# PHY_SFC.net
KiCad netlist of a schematic drawn in Altium Designer
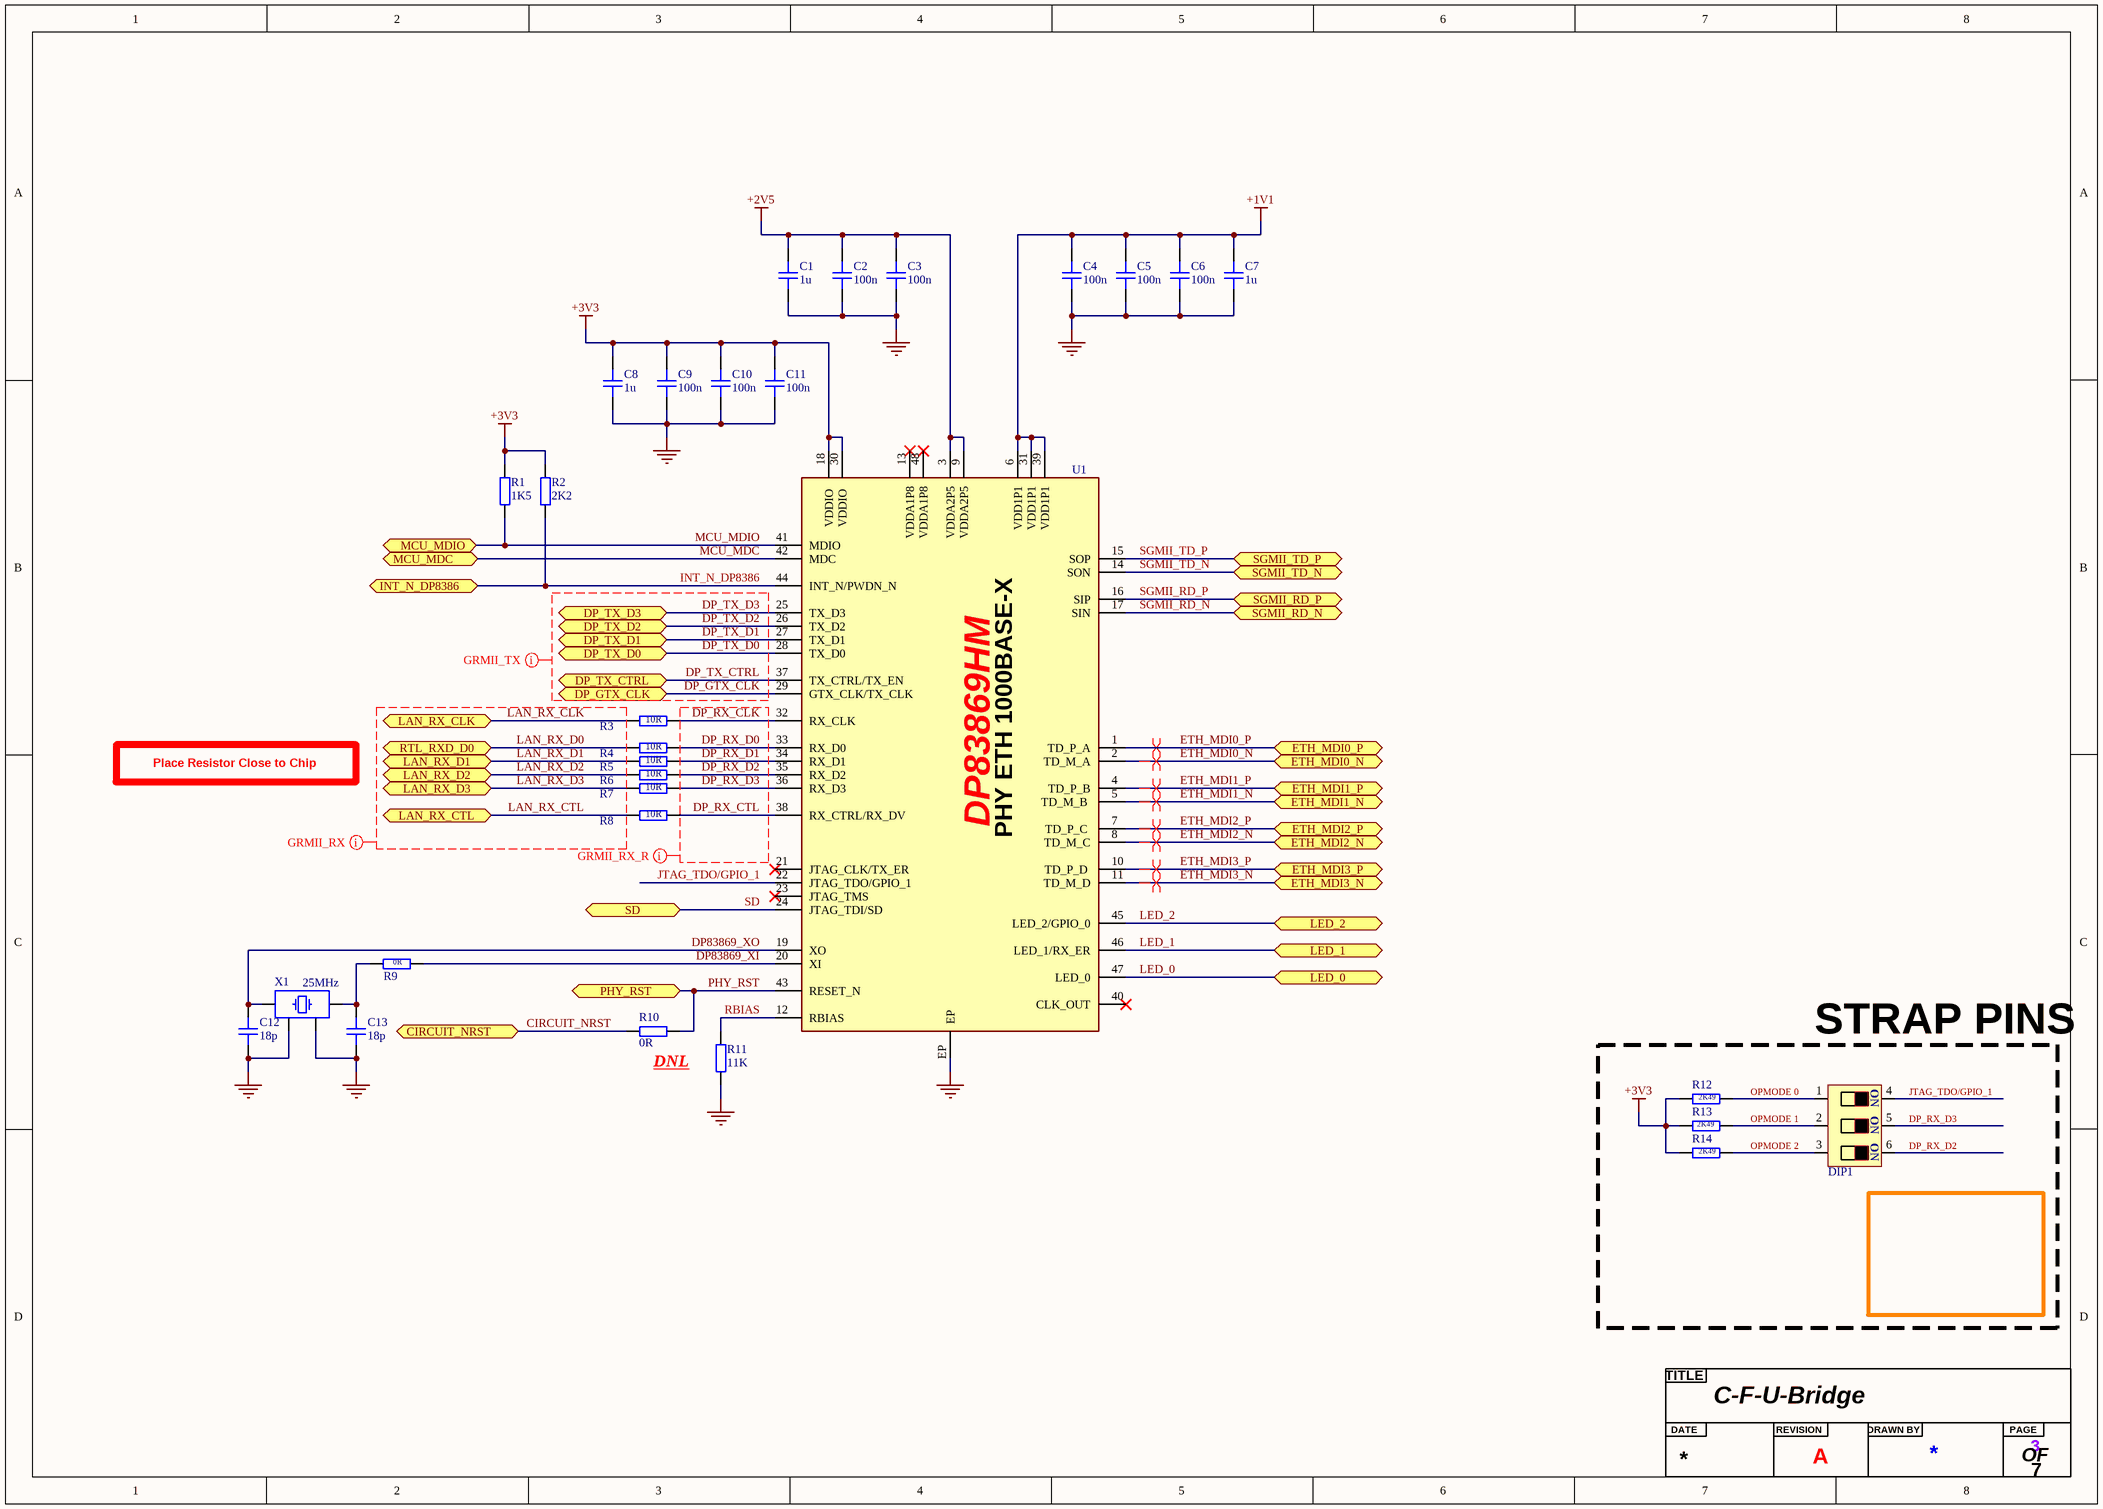
[diagram p0: PHY SFC.SchDoc]

(export (version "E")
  (design (tool "Eeschema 10.0.6"))
  (components
    (comp (ref "C1")
      (value "1u")
      (footprint "CAP_0603")
      (description "[C15849]")
      (libsource (lib "Schematic-Lib-PhilsLab") (part "CAP_0603"))
    )
    (comp (ref "C2")
      (value "100n")
      (footprint "CAP_0603")
      (description "[C14663]")
      (libsource (lib "Schematic-Lib-PhilsLab") (part "CAP_0603"))
    )
    (comp (ref "C3")
      (value "100n")
      (footprint "CAP_0603")
      (description "[C14663]")
      (libsource (lib "Schematic-Lib-PhilsLab") (part "CAP_0603"))
    )
    (comp (ref "C4")
      (value "100n")
      (footprint "CAP_0603")
      (description "[C14663]")
      (libsource (lib "Schematic-Lib-PhilsLab") (part "CAP_0603"))
    )
    (comp (ref "C5")
      (value "100n")
      (footprint "CAP_0603")
      (description "[C14663]")
      (libsource (lib "Schematic-Lib-PhilsLab") (part "CAP_0603"))
    )
    (comp (ref "C6")
      (value "100n")
      (footprint "CAP_0603")
      (description "[C14663]")
      (libsource (lib "Schematic-Lib-PhilsLab") (part "CAP_0603"))
    )
    (comp (ref "C7")
      (value "1u")
      (footprint "CAP_0603")
      (description "[C15849]")
      (libsource (lib "Schematic-Lib-PhilsLab") (part "CAP_0603"))
    )
    (comp (ref "C8")
      (value "1u")
      (footprint "CAP_0603")
      (description "[C15849]")
      (libsource (lib "Schematic-Lib-PhilsLab") (part "CAP_0603"))
    )
    (comp (ref "C9")
      (value "100n")
      (footprint "CAP_0603")
      (description "[C14663]")
      (libsource (lib "Schematic-Lib-PhilsLab") (part "CAP_0603"))
    )
    (comp (ref "C10")
      (value "100n")
      (footprint "CAP_0603")
      (description "[C14663]")
      (libsource (lib "Schematic-Lib-PhilsLab") (part "CAP_0603"))
    )
    (comp (ref "C11")
      (value "100n")
      (footprint "CAP_0603")
      (description "[C14663]")
      (libsource (lib "Schematic-Lib-PhilsLab") (part "CAP_0603"))
    )
    (comp (ref "C12")
      (value "18p")
      (footprint "CAP_0402")
      (description "Capacitor SMD 0402 [C1549]")
      (libsource (lib "Schematic-Lib-PhilsLab") (part "CAP_0402"))
    )
    (comp (ref "C13")
      (value "18p")
      (footprint "CAP_0402")
      (description "Capacitor SMD 0402 [C1549]")
      (libsource (lib "Schematic-Lib-PhilsLab") (part "CAP_0402"))
    )
    (comp (ref "DIP1")
      (value "3 POS DIP SWITCH")
      (footprint "DSWB03LHGET")
      (description "[C99420]")
      (libsource (lib "My_Library") (part "DSWB03LHGET"))
    )
    (comp (ref "R1")
      (value "1K5")
      (footprint "RES_0603")
      (description "[C22843]")
      (libsource (lib "Schematic-Lib-PhilsLab") (part "RES_0603"))
    )
    (comp (ref "R2")
      (value "2K2")
      (footprint "RES_0603")
      (description "[C4190]")
      (libsource (lib "Schematic-Lib-PhilsLab") (part "RES_0603"))
    )
    (comp (ref "R3")
      (value "10R")
      (footprint "RES_0402")
      (description "[C25077]")
      (libsource (lib "Schematic-Lib-PhilsLab") (part "RES_0402"))
    )
    (comp (ref "R4")
      (value "10R")
      (footprint "RES_0402")
      (description "[C25077]")
      (libsource (lib "Schematic-Lib-PhilsLab") (part "RES_0402"))
    )
    (comp (ref "R5")
      (value "10R")
      (footprint "RES_0402")
      (description "[C25077]")
      (libsource (lib "Schematic-Lib-PhilsLab") (part "RES_0402"))
    )
    (comp (ref "R6")
      (value "10R")
      (footprint "RES_0402")
      (description "[C25077]")
      (libsource (lib "Schematic-Lib-PhilsLab") (part "RES_0402"))
    )
    (comp (ref "R7")
      (value "10R")
      (footprint "RES_0402")
      (description "[C25077]")
      (libsource (lib "Schematic-Lib-PhilsLab") (part "RES_0402"))
    )
    (comp (ref "R8")
      (value "10R")
      (footprint "RES_0402")
      (description "[C25077]")
      (libsource (lib "Schematic-Lib-PhilsLab") (part "RES_0402"))
    )
    (comp (ref "R9")
      (value "0R")
      (footprint "RES_0402")
      (description "Resistor SMD 0402 [C17168]")
      (libsource (lib "Schematic-Lib-PhilsLab") (part "RES_0402"))
    )
    (comp (ref "R10")
      (value "0R")
      (footprint "RES_0603")
      (libsource (lib "Schematic-Lib-PhilsLab") (part "RES_0603"))
    )
    (comp (ref "R11")
      (value "11K")
      (footprint "RES_0603")
      (description "[C25950]")
      (libsource (lib "Schematic-Lib-PhilsLab") (part "RES_0603"))
    )
    (comp (ref "R12")
      (value "2K49")
      (footprint "RES_0603")
      (description "[C22908]")
      (libsource (lib "Schematic-Lib-PhilsLab") (part "RES_0603"))
    )
    (comp (ref "R13")
      (value "2K49")
      (footprint "RES_0603")
      (description "[C22908]")
      (libsource (lib "Schematic-Lib-PhilsLab") (part "RES_0603"))
    )
    (comp (ref "R14")
      (value "2K49")
      (footprint "RES_0603")
      (description "[C22908]")
      (libsource (lib "Schematic-Lib-PhilsLab") (part "RES_0603"))
    )
    (comp (ref "U1")
      (value "PHY ETH 1000BASE-X/1000BASE-T")
      (footprint "DP83869HMRGZT")
      (description "[C2671580]")
      (libsource (lib "My_Library") (part "DP83869HMRGZT"))
    )
    (comp (ref "X1")
      (value "25MHz")
      (footprint "XTAL_3225")
      (description "Crystal SMD 24MHz 10PPM 7pF 3225 [C9006]")
      (fields
        (field (name "MANUFACTURER") "Epson")
        (field (name "MANUFACTURER PART NUMBER") "TSX-3225 24.0000MF15X-AC")
      )
      (libsource (lib "Schematic-Lib-PhilsLab") (part "TSX-3225_24.0000MF15X-AC"))
    )
  )
  (nets
    (net (code "1") (name "+1V1") (class "Default")
      (node (ref "C4") (pin "2") (pinfunction "2_2") (pintype "passive"))
      (node (ref "C5") (pin "2") (pinfunction "2_2") (pintype "passive"))
      (node (ref "C6") (pin "2") (pinfunction "2_2") (pintype "passive"))
      (node (ref "C7") (pin "2") (pinfunction "2_2") (pintype "passive"))
      (node (ref "U1") (pin "31") (pinfunction "VDD1P1_31") (pintype "passive"))
      (node (ref "U1") (pin "39") (pinfunction "VDD1P1_39") (pintype "passive"))
      (node (ref "U1") (pin "6") (pinfunction "VDD1P1_6") (pintype "passive"))
    )
    (net (code "2") (name "+2V5") (class "Default")
      (node (ref "C1") (pin "2") (pinfunction "2_2") (pintype "passive"))
      (node (ref "C2") (pin "2") (pinfunction "2_2") (pintype "passive"))
      (node (ref "C3") (pin "2") (pinfunction "2_2") (pintype "passive"))
      (node (ref "U1") (pin "3") (pinfunction "VDDA2P5_3") (pintype "passive"))
      (node (ref "U1") (pin "9") (pinfunction "VDDA2P5_9") (pintype "passive"))
    )
    (net (code "3") (name "+3V3") (class "Default")
      (node (ref "C10") (pin "2") (pinfunction "2_2") (pintype "passive"))
      (node (ref "C11") (pin "2") (pinfunction "2_2") (pintype "passive"))
      (node (ref "C8") (pin "2") (pinfunction "2_2") (pintype "passive"))
      (node (ref "C9") (pin "2") (pinfunction "2_2") (pintype "passive"))
      (node (ref "R1") (pin "2") (pinfunction "2_2") (pintype "passive"))
      (node (ref "R12") (pin "2") (pinfunction "2_2") (pintype "passive"))
      (node (ref "R13") (pin "2") (pinfunction "2_2") (pintype "passive"))
      (node (ref "R14") (pin "2") (pinfunction "2_2") (pintype "passive"))
      (node (ref "R2") (pin "2") (pinfunction "2_2") (pintype "passive"))
      (node (ref "U1") (pin "18") (pinfunction "VDDIO_18") (pintype "passive"))
      (node (ref "U1") (pin "30") (pinfunction "VDDIO_30") (pintype "passive"))
    )
    (net (code "4") (name "/CIRCUIT_NRST") (class "Default")
      (node (ref "R10") (pin "1") (pinfunction "1_1") (pintype "passive"))
    )
    (net (code "5") (name "/DP83869_XI") (class "Default")
      (node (ref "R9") (pin "2") (pinfunction "2_2") (pintype "passive"))
      (node (ref "U1") (pin "20") (pinfunction "XI_20") (pintype "passive"))
    )
    (net (code "6") (name "/DP83869_XO") (class "Default")
      (node (ref "C12") (pin "2") (pinfunction "2_2") (pintype "passive"))
      (node (ref "U1") (pin "19") (pinfunction "XO_19") (pintype "passive"))
      (node (ref "X1") (pin "3") (pinfunction "3_3") (pintype "passive"))
    )
    (net (code "7") (name "/DP_GTX_CLK") (class "Default")
      (node (ref "U1") (pin "29") (pinfunction "GTX_CLK/TX_CLK_29") (pintype "passive"))
    )
    (net (code "8") (name "/DP_RX_CLK") (class "Default")
      (node (ref "R3") (pin "2") (pinfunction "2_2") (pintype "passive"))
      (node (ref "U1") (pin "32") (pinfunction "RX_CLK_32") (pintype "passive"))
    )
    (net (code "9") (name "/DP_RX_CTL") (class "Default")
      (node (ref "R8") (pin "2") (pinfunction "2_2") (pintype "passive"))
      (node (ref "U1") (pin "38") (pinfunction "RX_CTRL/RX_DV_38") (pintype "passive"))
    )
    (net (code "10") (name "/DP_RX_D0") (class "Default")
      (node (ref "R4") (pin "2") (pinfunction "2_2") (pintype "passive"))
      (node (ref "U1") (pin "33") (pinfunction "RX_D0_33") (pintype "passive"))
    )
    (net (code "11") (name "/DP_RX_D1") (class "Default")
      (node (ref "R5") (pin "2") (pinfunction "2_2") (pintype "passive"))
      (node (ref "U1") (pin "34") (pinfunction "RX_D1_34") (pintype "passive"))
    )
    (net (code "12") (name "/DP_RX_D2") (class "Default")
      (node (ref "DIP1") (pin "6") (pinfunction "6_6") (pintype "passive"))
      (node (ref "R6") (pin "2") (pinfunction "2_2") (pintype "passive"))
      (node (ref "U1") (pin "35") (pinfunction "RX_D2_35") (pintype "passive"))
    )
    (net (code "13") (name "/DP_RX_D3") (class "Default")
      (node (ref "DIP1") (pin "5") (pinfunction "5_5") (pintype "passive"))
      (node (ref "R7") (pin "2") (pinfunction "2_2") (pintype "passive"))
      (node (ref "U1") (pin "36") (pinfunction "RX_D3_36") (pintype "passive"))
    )
    (net (code "14") (name "/DP_TX_CTRL") (class "Default")
      (node (ref "U1") (pin "37") (pinfunction "TX_CTRL/TX_EN_37") (pintype "passive"))
    )
    (net (code "15") (name "/DP_TX_D0") (class "Default")
      (node (ref "U1") (pin "28") (pinfunction "TX_D0_28") (pintype "passive"))
    )
    (net (code "16") (name "/DP_TX_D1") (class "Default")
      (node (ref "U1") (pin "27") (pinfunction "TX_D1_27") (pintype "passive"))
    )
    (net (code "17") (name "/DP_TX_D2") (class "Default")
      (node (ref "U1") (pin "26") (pinfunction "TX_D2_26") (pintype "passive"))
    )
    (net (code "18") (name "/DP_TX_D3") (class "Default")
      (node (ref "U1") (pin "25") (pinfunction "TX_D3_25") (pintype "passive"))
    )
    (net (code "19") (name "/ETH_MDI0_N") (class "Default")
      (node (ref "U1") (pin "2") (pinfunction "TD_M_A_2") (pintype "passive"))
    )
    (net (code "20") (name "/ETH_MDI0_P") (class "Default")
      (node (ref "U1") (pin "1") (pinfunction "TD_P_A_1") (pintype "passive"))
    )
    (net (code "21") (name "/ETH_MDI1_N") (class "Default")
      (node (ref "U1") (pin "5") (pinfunction "TD_M_B_5") (pintype "passive"))
    )
    (net (code "22") (name "/ETH_MDI1_P") (class "Default")
      (node (ref "U1") (pin "4") (pinfunction "TD_P_B_4") (pintype "passive"))
    )
    (net (code "23") (name "/ETH_MDI2_N") (class "Default")
      (node (ref "U1") (pin "8") (pinfunction "TD_M_C_8") (pintype "passive"))
    )
    (net (code "24") (name "/ETH_MDI2_P") (class "Default")
      (node (ref "U1") (pin "7") (pinfunction "TD_P_C_7") (pintype "passive"))
    )
    (net (code "25") (name "/ETH_MDI3_N") (class "Default")
      (node (ref "U1") (pin "11") (pinfunction "TD_M_D_11") (pintype "passive"))
    )
    (net (code "26") (name "/ETH_MDI3_P") (class "Default")
      (node (ref "U1") (pin "10") (pinfunction "TD_P_D_10") (pintype "passive"))
    )
    (net (code "27") (name "/INT_N_DP8386") (class "Default")
      (node (ref "R2") (pin "1") (pinfunction "1_1") (pintype "passive"))
      (node (ref "U1") (pin "44") (pinfunction "INT_N/PWDN_N_44") (pintype "passive"))
    )
    (net (code "28") (name "/JTAG_TDO{slash}GPIO_1") (class "Default")
      (node (ref "DIP1") (pin "4") (pinfunction "4_4") (pintype "passive"))
      (node (ref "U1") (pin "22") (pinfunction "JTAG_TDO/GPIO_1_22") (pintype "passive"))
    )
    (net (code "29") (name "/LAN_RX_CLK") (class "Default")
      (node (ref "R3") (pin "1") (pinfunction "1_1") (pintype "passive"))
    )
    (net (code "30") (name "/LAN_RX_CTL") (class "Default")
      (node (ref "R8") (pin "1") (pinfunction "1_1") (pintype "passive"))
    )
    (net (code "31") (name "/LAN_RX_D0") (class "Default")
      (node (ref "R4") (pin "1") (pinfunction "1_1") (pintype "passive"))
    )
    (net (code "32") (name "/LAN_RX_D1") (class "Default")
      (node (ref "R5") (pin "1") (pinfunction "1_1") (pintype "passive"))
    )
    (net (code "33") (name "/LAN_RX_D2") (class "Default")
      (node (ref "R6") (pin "1") (pinfunction "1_1") (pintype "passive"))
    )
    (net (code "34") (name "/LAN_RX_D3") (class "Default")
      (node (ref "R7") (pin "1") (pinfunction "1_1") (pintype "passive"))
    )
    (net (code "35") (name "/LED_0") (class "Default")
      (node (ref "U1") (pin "47") (pinfunction "LED_0_47") (pintype "passive"))
    )
    (net (code "36") (name "/LED_1") (class "Default")
      (node (ref "U1") (pin "46") (pinfunction "LED_1/RX_ER_46") (pintype "passive"))
    )
    (net (code "37") (name "/LED_2") (class "Default")
      (node (ref "U1") (pin "45") (pinfunction "LED_2/GPIO_0_45") (pintype "passive"))
    )
    (net (code "38") (name "/MCU_MDC") (class "Default")
      (node (ref "U1") (pin "42") (pinfunction "MDC_42") (pintype "passive"))
    )
    (net (code "39") (name "/MCU_MDIO") (class "Default")
      (node (ref "R1") (pin "1") (pinfunction "1_1") (pintype "passive"))
      (node (ref "U1") (pin "41") (pinfunction "MDIO_41") (pintype "passive"))
    )
    (net (code "40") (name "/OPMODE 0") (class "Default")
      (node (ref "DIP1") (pin "1") (pinfunction "1_1") (pintype "passive"))
      (node (ref "R12") (pin "1") (pinfunction "1_1") (pintype "passive"))
    )
    (net (code "41") (name "/OPMODE 1") (class "Default")
      (node (ref "DIP1") (pin "2") (pinfunction "2_2") (pintype "passive"))
      (node (ref "R13") (pin "1") (pinfunction "1_1") (pintype "passive"))
    )
    (net (code "42") (name "/OPMODE 2") (class "Default")
      (node (ref "DIP1") (pin "3") (pinfunction "3_3") (pintype "passive"))
      (node (ref "R14") (pin "1") (pinfunction "1_1") (pintype "passive"))
    )
    (net (code "43") (name "/PHY_RST") (class "Default")
      (node (ref "R10") (pin "2") (pinfunction "2_2") (pintype "passive"))
      (node (ref "U1") (pin "43") (pinfunction "RESET_N_43") (pintype "passive"))
    )
    (net (code "44") (name "/RBIAS") (class "Default")
      (node (ref "R11") (pin "2") (pinfunction "2_2") (pintype "passive"))
      (node (ref "U1") (pin "12") (pinfunction "RBIAS_12") (pintype "passive"))
    )
    (net (code "45") (name "/SD") (class "Default")
      (node (ref "U1") (pin "24") (pinfunction "JTAG_TDI/SD_24") (pintype "passive"))
    )
    (net (code "46") (name "/SGMII_RD_N") (class "Default")
      (node (ref "U1") (pin "17") (pinfunction "SIN_17") (pintype "passive"))
    )
    (net (code "47") (name "/SGMII_RD_P") (class "Default")
      (node (ref "U1") (pin "16") (pinfunction "SIP_16") (pintype "passive"))
    )
    (net (code "48") (name "/SGMII_TD_N") (class "Default")
      (node (ref "U1") (pin "14") (pinfunction "SON_14") (pintype "passive"))
    )
    (net (code "49") (name "/SGMII_TD_P") (class "Default")
      (node (ref "U1") (pin "15") (pinfunction "SOP_15") (pintype "passive"))
    )
    (net (code "50") (name "GND") (class "Default")
      (node (ref "C1") (pin "1") (pinfunction "1_1") (pintype "passive"))
      (node (ref "C10") (pin "1") (pinfunction "1_1") (pintype "passive"))
      (node (ref "C11") (pin "1") (pinfunction "1_1") (pintype "passive"))
      (node (ref "C12") (pin "1") (pinfunction "1_1") (pintype "passive"))
      (node (ref "C13") (pin "1") (pinfunction "1_1") (pintype "passive"))
      (node (ref "C2") (pin "1") (pinfunction "1_1") (pintype "passive"))
      (node (ref "C3") (pin "1") (pinfunction "1_1") (pintype "passive"))
      (node (ref "C4") (pin "1") (pinfunction "1_1") (pintype "passive"))
      (node (ref "C5") (pin "1") (pinfunction "1_1") (pintype "passive"))
      (node (ref "C6") (pin "1") (pinfunction "1_1") (pintype "passive"))
      (node (ref "C7") (pin "1") (pinfunction "1_1") (pintype "passive"))
      (node (ref "C8") (pin "1") (pinfunction "1_1") (pintype "passive"))
      (node (ref "C9") (pin "1") (pinfunction "1_1") (pintype "passive"))
      (node (ref "R11") (pin "1") (pinfunction "1_1") (pintype "passive"))
      (node (ref "U1") (pin "EP") (pinfunction "EP_EP") (pintype "passive"))
      (node (ref "X1") (pin "2") (pinfunction "2_2") (pintype "passive"))
      (node (ref "X1") (pin "4") (pinfunction "4_4") (pintype "passive"))
    )
    (net (code "51") (name "Net-(C13-Pad2)") (class "Default")
      (node (ref "C13") (pin "2") (pinfunction "2_2") (pintype "passive"))
      (node (ref "R9") (pin "1") (pinfunction "1_1") (pintype "passive"))
      (node (ref "X1") (pin "1") (pinfunction "1_1") (pintype "passive"))
    )
    (net (code "52") (name "unconnected-(U1-CLK_OUT-Pad40)") (class "Default")
      (node (ref "U1") (pin "40") (pinfunction "CLK_OUT_40") (pintype "passive+no_connect"))
    )
    (net (code "53") (name "unconnected-(U1-JTAG_CLK{slash}TX_ER-Pad21)") (class "Default")
      (node (ref "U1") (pin "21") (pinfunction "JTAG_CLK/TX_ER_21") (pintype "passive+no_connect"))
    )
    (net (code "54") (name "unconnected-(U1-JTAG_TMS-Pad23)") (class "Default")
      (node (ref "U1") (pin "23") (pinfunction "JTAG_TMS_23") (pintype "passive+no_connect"))
    )
    (net (code "55") (name "unconnected-(U1-VDDA1P8-Pad13)") (class "Default")
      (node (ref "U1") (pin "13") (pinfunction "VDDA1P8_13") (pintype "passive+no_connect"))
    )
    (net (code "56") (name "unconnected-(U1-VDDA1P8-Pad48)") (class "Default")
      (node (ref "U1") (pin "48") (pinfunction "VDDA1P8_48") (pintype "passive+no_connect"))
    )
  )
)
